# FLC_Circuit.net
KiCad netlist of a schematic drawn in EAGLE
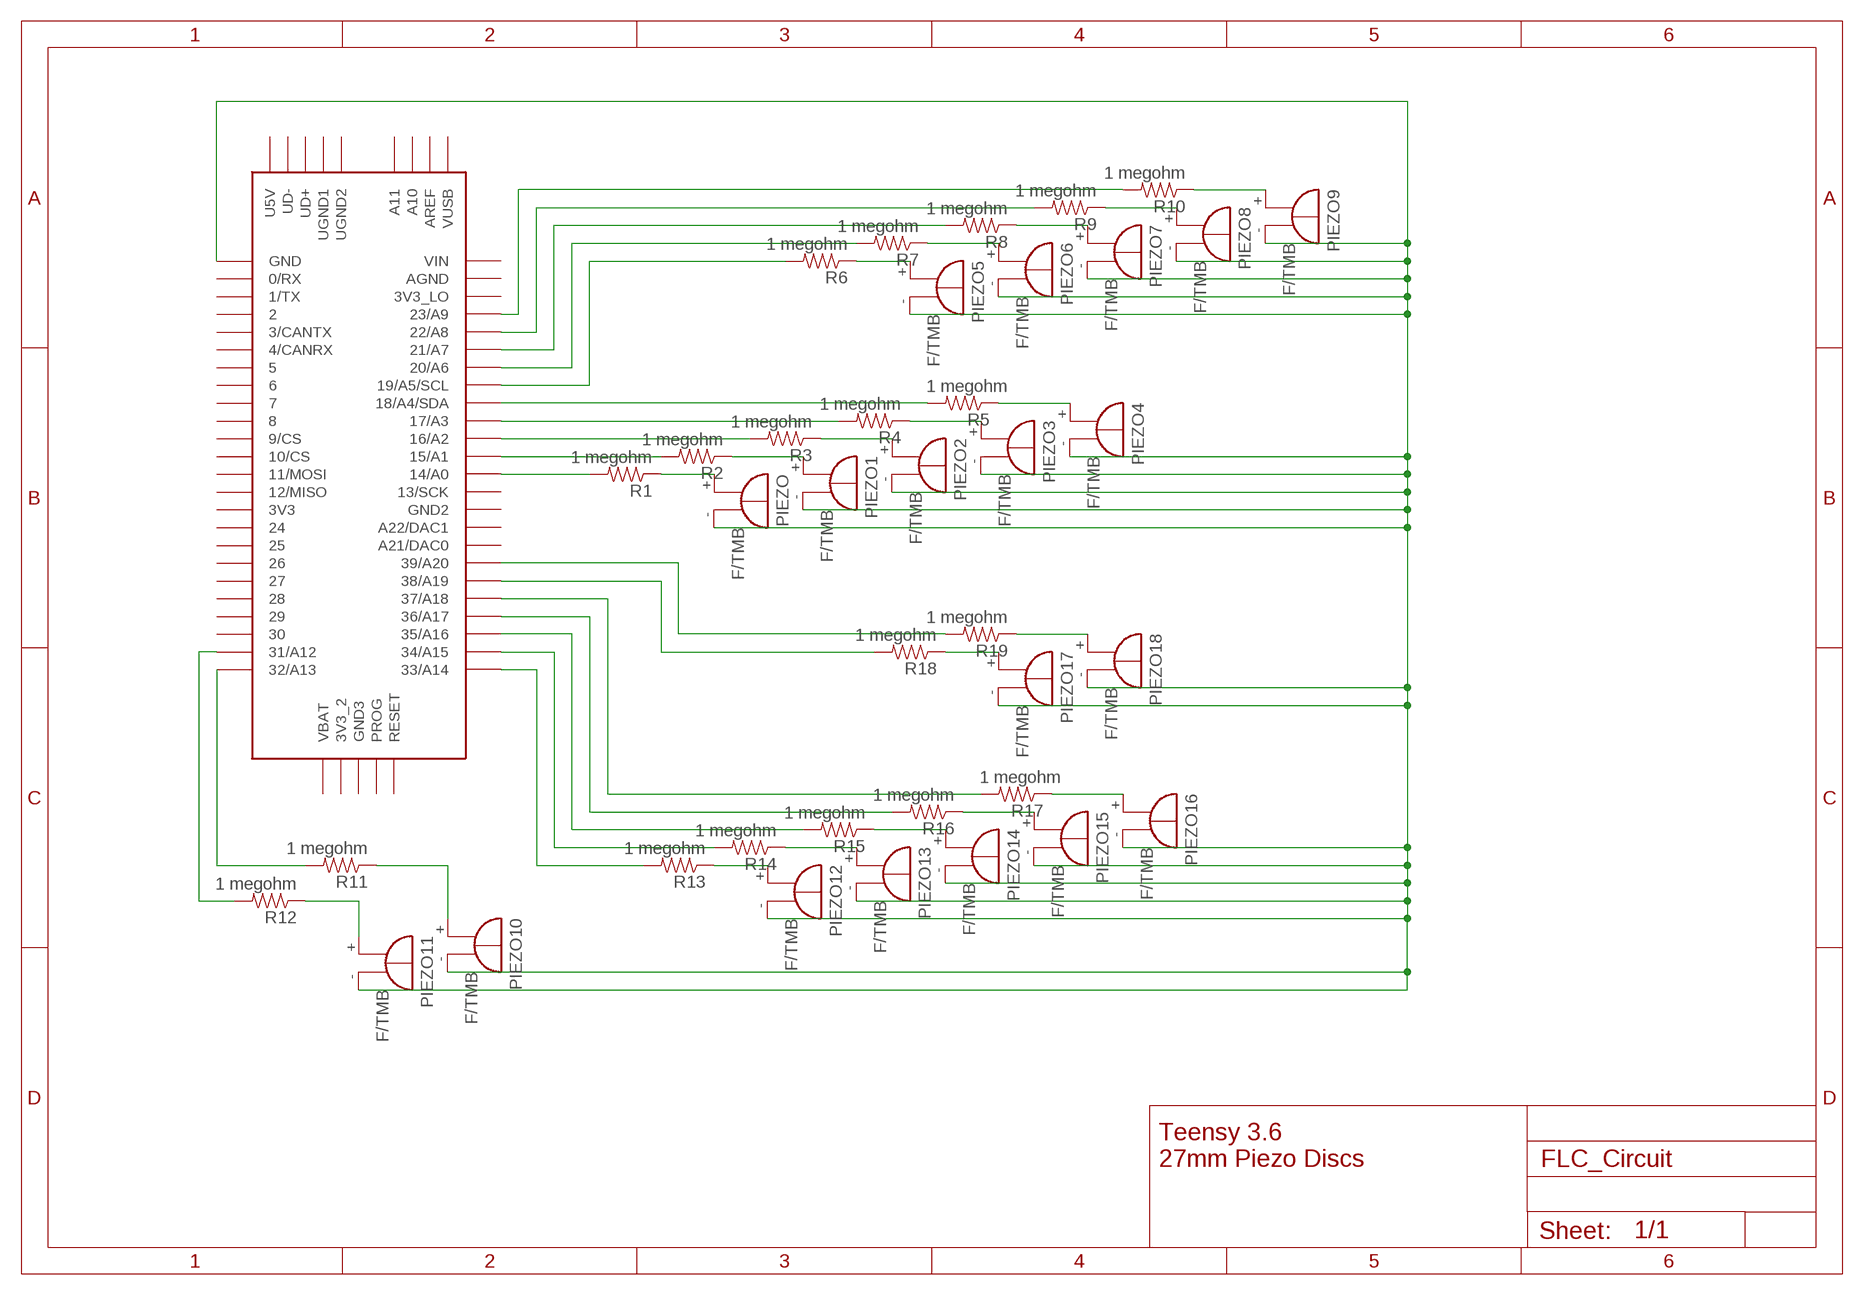
[diagram p0: schematic, sheet 1]

(export (version "E")
  (design (tool "Eeschema 10.0.6"))
  (components
    (comp (ref "PIEZO")
      (value "F/TMB")
      (footprint "eagle-import:F_TMB")
      (libsource (lib "eagle-import") (part "F/TMB"))
    )
    (comp (ref "PIEZO1")
      (value "F/TMB")
      (footprint "eagle-import:F_TMB")
      (libsource (lib "eagle-import") (part "F/TMB"))
    )
    (comp (ref "PIEZO2")
      (value "F/TMB")
      (footprint "eagle-import:F_TMB")
      (libsource (lib "eagle-import") (part "F/TMB"))
    )
    (comp (ref "PIEZO3")
      (value "F/TMB")
      (footprint "eagle-import:F_TMB")
      (libsource (lib "eagle-import") (part "F/TMB"))
    )
    (comp (ref "PIEZO4")
      (value "F/TMB")
      (footprint "eagle-import:F_TMB")
      (libsource (lib "eagle-import") (part "F/TMB"))
    )
    (comp (ref "PIEZO5")
      (value "F/TMB")
      (footprint "eagle-import:F_TMB")
      (libsource (lib "eagle-import") (part "F/TMB"))
    )
    (comp (ref "PIEZO6")
      (value "F/TMB")
      (footprint "eagle-import:F_TMB")
      (libsource (lib "eagle-import") (part "F/TMB"))
    )
    (comp (ref "PIEZO7")
      (value "F/TMB")
      (footprint "eagle-import:F_TMB")
      (libsource (lib "eagle-import") (part "F/TMB"))
    )
    (comp (ref "PIEZO8")
      (value "F/TMB")
      (footprint "eagle-import:F_TMB")
      (libsource (lib "eagle-import") (part "F/TMB"))
    )
    (comp (ref "PIEZO9")
      (value "F/TMB")
      (footprint "eagle-import:F_TMB")
      (libsource (lib "eagle-import") (part "F/TMB"))
    )
    (comp (ref "PIEZO10")
      (value "F/TMB")
      (footprint "eagle-import:F_TMB")
      (libsource (lib "eagle-import") (part "F/TMB"))
    )
    (comp (ref "PIEZO11")
      (value "F/TMB")
      (footprint "eagle-import:F_TMB")
      (libsource (lib "eagle-import") (part "F/TMB"))
    )
    (comp (ref "PIEZO12")
      (value "F/TMB")
      (footprint "eagle-import:F_TMB")
      (libsource (lib "eagle-import") (part "F/TMB"))
    )
    (comp (ref "PIEZO13")
      (value "F/TMB")
      (footprint "eagle-import:F_TMB")
      (libsource (lib "eagle-import") (part "F/TMB"))
    )
    (comp (ref "PIEZO14")
      (value "F/TMB")
      (footprint "eagle-import:F_TMB")
      (libsource (lib "eagle-import") (part "F/TMB"))
    )
    (comp (ref "PIEZO15")
      (value "F/TMB")
      (footprint "eagle-import:F_TMB")
      (libsource (lib "eagle-import") (part "F/TMB"))
    )
    (comp (ref "PIEZO16")
      (value "F/TMB")
      (footprint "eagle-import:F_TMB")
      (libsource (lib "eagle-import") (part "F/TMB"))
    )
    (comp (ref "PIEZO17")
      (value "F/TMB")
      (footprint "eagle-import:F_TMB")
      (libsource (lib "eagle-import") (part "F/TMB"))
    )
    (comp (ref "PIEZO18")
      (value "F/TMB")
      (footprint "eagle-import:F_TMB")
      (libsource (lib "eagle-import") (part "F/TMB"))
    )
    (comp (ref "R1")
      (value "1 megohm")
      (footprint "eagle-import:0805")
      (libsource (lib "eagle-import") (part "COMPONENT_RESISTOR-0805"))
    )
    (comp (ref "R2")
      (value "1 megohm")
      (footprint "eagle-import:0805")
      (libsource (lib "eagle-import") (part "COMPONENT_RESISTOR-0805"))
    )
    (comp (ref "R3")
      (value "1 megohm")
      (footprint "eagle-import:0805")
      (libsource (lib "eagle-import") (part "COMPONENT_RESISTOR-0805"))
    )
    (comp (ref "R4")
      (value "1 megohm")
      (footprint "eagle-import:0805")
      (libsource (lib "eagle-import") (part "COMPONENT_RESISTOR-0805"))
    )
    (comp (ref "R5")
      (value "1 megohm")
      (footprint "eagle-import:0805")
      (libsource (lib "eagle-import") (part "COMPONENT_RESISTOR-0805"))
    )
    (comp (ref "R6")
      (value "1 megohm")
      (footprint "eagle-import:0805")
      (libsource (lib "eagle-import") (part "COMPONENT_RESISTOR-0805"))
    )
    (comp (ref "R7")
      (value "1 megohm")
      (footprint "eagle-import:0805")
      (libsource (lib "eagle-import") (part "COMPONENT_RESISTOR-0805"))
    )
    (comp (ref "R8")
      (value "1 megohm")
      (footprint "eagle-import:0805")
      (libsource (lib "eagle-import") (part "COMPONENT_RESISTOR-0805"))
    )
    (comp (ref "R9")
      (value "1 megohm")
      (footprint "eagle-import:0805")
      (libsource (lib "eagle-import") (part "COMPONENT_RESISTOR-0805"))
    )
    (comp (ref "R10")
      (value "1 megohm")
      (footprint "eagle-import:0805")
      (libsource (lib "eagle-import") (part "COMPONENT_RESISTOR-0805"))
    )
    (comp (ref "R11")
      (value "1 megohm")
      (footprint "eagle-import:0805")
      (libsource (lib "eagle-import") (part "COMPONENT_RESISTOR-0805"))
    )
    (comp (ref "R12")
      (value "1 megohm")
      (footprint "eagle-import:0805")
      (libsource (lib "eagle-import") (part "COMPONENT_RESISTOR-0805"))
    )
    (comp (ref "R13")
      (value "1 megohm")
      (footprint "eagle-import:0805")
      (libsource (lib "eagle-import") (part "COMPONENT_RESISTOR-0805"))
    )
    (comp (ref "R14")
      (value "1 megohm")
      (footprint "eagle-import:0805")
      (libsource (lib "eagle-import") (part "COMPONENT_RESISTOR-0805"))
    )
    (comp (ref "R15")
      (value "1 megohm")
      (footprint "eagle-import:0805")
      (libsource (lib "eagle-import") (part "COMPONENT_RESISTOR-0805"))
    )
    (comp (ref "R16")
      (value "1 megohm")
      (footprint "eagle-import:0805")
      (libsource (lib "eagle-import") (part "COMPONENT_RESISTOR-0805"))
    )
    (comp (ref "R17")
      (value "1 megohm")
      (footprint "eagle-import:0805")
      (libsource (lib "eagle-import") (part "COMPONENT_RESISTOR-0805"))
    )
    (comp (ref "R18")
      (value "1 megohm")
      (footprint "eagle-import:0805")
      (libsource (lib "eagle-import") (part "COMPONENT_RESISTOR-0805"))
    )
    (comp (ref "R19")
      (value "1 megohm")
      (footprint "eagle-import:0805")
      (libsource (lib "eagle-import") (part "COMPONENT_RESISTOR-0805"))
    )
    (comp (ref "U$1")
      (value "TEENSY_3.5/3.6")
      (footprint "eagle-import:TEENSY_3.5_3.6")
      (libsource (lib "eagle-import") (part "TEENSY_3.5/3.6"))
    )
  )
  (nets
    (net (code "1") (name "Net-(PIEZO-Pad+)") (class "Default")
      (node (ref "PIEZO") (pin "+") (pinfunction "+_+") (pintype "passive"))
      (node (ref "R1") (pin "1") (pinfunction "1_1") (pintype "passive"))
    )
    (net (code "2") (name "Net-(PIEZO-Pad-)") (class "Default")
      (node (ref "PIEZO") (pin "-") (pinfunction "-_-") (pintype "passive"))
      (node (ref "PIEZO1") (pin "-") (pinfunction "-_-") (pintype "passive"))
      (node (ref "PIEZO10") (pin "-") (pinfunction "-_-") (pintype "passive"))
      (node (ref "PIEZO11") (pin "-") (pinfunction "-_-") (pintype "passive"))
      (node (ref "PIEZO12") (pin "-") (pinfunction "-_-") (pintype "passive"))
      (node (ref "PIEZO13") (pin "-") (pinfunction "-_-") (pintype "passive"))
      (node (ref "PIEZO14") (pin "-") (pinfunction "-_-") (pintype "passive"))
      (node (ref "PIEZO15") (pin "-") (pinfunction "-_-") (pintype "passive"))
      (node (ref "PIEZO16") (pin "-") (pinfunction "-_-") (pintype "passive"))
      (node (ref "PIEZO17") (pin "-") (pinfunction "-_-") (pintype "passive"))
      (node (ref "PIEZO18") (pin "-") (pinfunction "-_-") (pintype "passive"))
      (node (ref "PIEZO2") (pin "-") (pinfunction "-_-") (pintype "passive"))
      (node (ref "PIEZO3") (pin "-") (pinfunction "-_-") (pintype "passive"))
      (node (ref "PIEZO4") (pin "-") (pinfunction "-_-") (pintype "passive"))
      (node (ref "PIEZO5") (pin "-") (pinfunction "-_-") (pintype "passive"))
      (node (ref "PIEZO6") (pin "-") (pinfunction "-_-") (pintype "passive"))
      (node (ref "PIEZO7") (pin "-") (pinfunction "-_-") (pintype "passive"))
      (node (ref "PIEZO8") (pin "-") (pinfunction "-_-") (pintype "passive"))
      (node (ref "PIEZO9") (pin "-") (pinfunction "-_-") (pintype "passive"))
      (node (ref "U$1") (pin "GND") (pinfunction "GND_GND") (pintype "bidirectional"))
    )
    (net (code "3") (name "Net-(PIEZO1-Pad+)") (class "Default")
      (node (ref "PIEZO1") (pin "+") (pinfunction "+_+") (pintype "passive"))
      (node (ref "R2") (pin "1") (pinfunction "1_1") (pintype "passive"))
    )
    (net (code "4") (name "Net-(PIEZO2-Pad+)") (class "Default")
      (node (ref "PIEZO2") (pin "+") (pinfunction "+_+") (pintype "passive"))
      (node (ref "R3") (pin "1") (pinfunction "1_1") (pintype "passive"))
    )
    (net (code "5") (name "Net-(PIEZO3-Pad+)") (class "Default")
      (node (ref "PIEZO3") (pin "+") (pinfunction "+_+") (pintype "passive"))
      (node (ref "R4") (pin "1") (pinfunction "1_1") (pintype "passive"))
    )
    (net (code "6") (name "Net-(PIEZO4-Pad+)") (class "Default")
      (node (ref "PIEZO4") (pin "+") (pinfunction "+_+") (pintype "passive"))
      (node (ref "R5") (pin "1") (pinfunction "1_1") (pintype "passive"))
    )
    (net (code "7") (name "Net-(PIEZO5-Pad+)") (class "Default")
      (node (ref "PIEZO5") (pin "+") (pinfunction "+_+") (pintype "passive"))
      (node (ref "R6") (pin "1") (pinfunction "1_1") (pintype "passive"))
    )
    (net (code "8") (name "Net-(PIEZO6-Pad+)") (class "Default")
      (node (ref "PIEZO6") (pin "+") (pinfunction "+_+") (pintype "passive"))
      (node (ref "R7") (pin "1") (pinfunction "1_1") (pintype "passive"))
    )
    (net (code "9") (name "Net-(PIEZO7-Pad+)") (class "Default")
      (node (ref "PIEZO7") (pin "+") (pinfunction "+_+") (pintype "passive"))
      (node (ref "R8") (pin "1") (pinfunction "1_1") (pintype "passive"))
    )
    (net (code "10") (name "Net-(PIEZO8-Pad+)") (class "Default")
      (node (ref "PIEZO8") (pin "+") (pinfunction "+_+") (pintype "passive"))
      (node (ref "R9") (pin "1") (pinfunction "1_1") (pintype "passive"))
    )
    (net (code "11") (name "Net-(PIEZO9-Pad+)") (class "Default")
      (node (ref "PIEZO9") (pin "+") (pinfunction "+_+") (pintype "passive"))
      (node (ref "R10") (pin "1") (pinfunction "1_1") (pintype "passive"))
    )
    (net (code "12") (name "Net-(PIEZO10-Pad+)") (class "Default")
      (node (ref "PIEZO10") (pin "+") (pinfunction "+_+") (pintype "passive"))
      (node (ref "R11") (pin "1") (pinfunction "1_1") (pintype "passive"))
    )
    (net (code "13") (name "Net-(PIEZO11-Pad+)") (class "Default")
      (node (ref "PIEZO11") (pin "+") (pinfunction "+_+") (pintype "passive"))
      (node (ref "R12") (pin "1") (pinfunction "1_1") (pintype "passive"))
    )
    (net (code "14") (name "Net-(PIEZO12-Pad+)") (class "Default")
      (node (ref "PIEZO12") (pin "+") (pinfunction "+_+") (pintype "passive"))
      (node (ref "R13") (pin "1") (pinfunction "1_1") (pintype "passive"))
    )
    (net (code "15") (name "Net-(PIEZO13-Pad+)") (class "Default")
      (node (ref "PIEZO13") (pin "+") (pinfunction "+_+") (pintype "passive"))
      (node (ref "R14") (pin "1") (pinfunction "1_1") (pintype "passive"))
    )
    (net (code "16") (name "Net-(PIEZO14-Pad+)") (class "Default")
      (node (ref "PIEZO14") (pin "+") (pinfunction "+_+") (pintype "passive"))
      (node (ref "R15") (pin "1") (pinfunction "1_1") (pintype "passive"))
    )
    (net (code "17") (name "Net-(PIEZO15-Pad+)") (class "Default")
      (node (ref "PIEZO15") (pin "+") (pinfunction "+_+") (pintype "passive"))
      (node (ref "R16") (pin "1") (pinfunction "1_1") (pintype "passive"))
    )
    (net (code "18") (name "Net-(PIEZO16-Pad+)") (class "Default")
      (node (ref "PIEZO16") (pin "+") (pinfunction "+_+") (pintype "passive"))
      (node (ref "R17") (pin "1") (pinfunction "1_1") (pintype "passive"))
    )
    (net (code "19") (name "Net-(PIEZO17-Pad+)") (class "Default")
      (node (ref "PIEZO17") (pin "+") (pinfunction "+_+") (pintype "passive"))
      (node (ref "R18") (pin "1") (pinfunction "1_1") (pintype "passive"))
    )
    (net (code "20") (name "Net-(PIEZO18-Pad+)") (class "Default")
      (node (ref "PIEZO18") (pin "+") (pinfunction "+_+") (pintype "passive"))
      (node (ref "R19") (pin "1") (pinfunction "1_1") (pintype "passive"))
    )
    (net (code "21") (name "Net-(R1-Pad2)") (class "Default")
      (node (ref "R1") (pin "2") (pinfunction "2_2") (pintype "passive"))
      (node (ref "U$1") (pin "14/A0") (pinfunction "14/A0_14/A0") (pintype "bidirectional"))
    )
    (net (code "22") (name "Net-(R2-Pad2)") (class "Default")
      (node (ref "R2") (pin "2") (pinfunction "2_2") (pintype "passive"))
      (node (ref "U$1") (pin "15/A1") (pinfunction "15/A1_15/A1") (pintype "bidirectional"))
    )
    (net (code "23") (name "Net-(R3-Pad2)") (class "Default")
      (node (ref "R3") (pin "2") (pinfunction "2_2") (pintype "passive"))
      (node (ref "U$1") (pin "16/A2") (pinfunction "16/A2_16/A2") (pintype "bidirectional"))
    )
    (net (code "24") (name "Net-(R4-Pad2)") (class "Default")
      (node (ref "R4") (pin "2") (pinfunction "2_2") (pintype "passive"))
      (node (ref "U$1") (pin "17/A3") (pinfunction "17/A3_17/A3") (pintype "bidirectional"))
    )
    (net (code "25") (name "Net-(R5-Pad2)") (class "Default")
      (node (ref "R5") (pin "2") (pinfunction "2_2") (pintype "passive"))
      (node (ref "U$1") (pin "18/A4/SDA") (pinfunction "18/A4/SDA_18/A4/SDA") (pintype "bidirectional"))
    )
    (net (code "26") (name "Net-(R6-Pad2)") (class "Default")
      (node (ref "R6") (pin "2") (pinfunction "2_2") (pintype "passive"))
      (node (ref "U$1") (pin "19/A5/SCL") (pinfunction "19/A5/SCL_19/A5/SCL") (pintype "bidirectional"))
    )
    (net (code "27") (name "Net-(R7-Pad2)") (class "Default")
      (node (ref "R7") (pin "2") (pinfunction "2_2") (pintype "passive"))
      (node (ref "U$1") (pin "20/A6") (pinfunction "20/A6_20/A6") (pintype "bidirectional"))
    )
    (net (code "28") (name "Net-(R8-Pad2)") (class "Default")
      (node (ref "R8") (pin "2") (pinfunction "2_2") (pintype "passive"))
      (node (ref "U$1") (pin "21/A7") (pinfunction "21/A7_21/A7") (pintype "bidirectional"))
    )
    (net (code "29") (name "Net-(R9-Pad2)") (class "Default")
      (node (ref "R9") (pin "2") (pinfunction "2_2") (pintype "passive"))
      (node (ref "U$1") (pin "22/A8") (pinfunction "22/A8_22/A8") (pintype "bidirectional"))
    )
    (net (code "30") (name "Net-(R10-Pad2)") (class "Default")
      (node (ref "R10") (pin "2") (pinfunction "2_2") (pintype "passive"))
      (node (ref "U$1") (pin "23/A9") (pinfunction "23/A9_23/A9") (pintype "bidirectional"))
    )
    (net (code "31") (name "Net-(R11-Pad2)") (class "Default")
      (node (ref "R11") (pin "2") (pinfunction "2_2") (pintype "passive"))
      (node (ref "U$1") (pin "32/A13") (pinfunction "32/A13_32/A13") (pintype "bidirectional"))
    )
    (net (code "32") (name "Net-(R12-Pad2)") (class "Default")
      (node (ref "R12") (pin "2") (pinfunction "2_2") (pintype "passive"))
      (node (ref "U$1") (pin "31/A12") (pinfunction "31/A12_31/A12") (pintype "bidirectional"))
    )
    (net (code "33") (name "Net-(R13-Pad2)") (class "Default")
      (node (ref "R13") (pin "2") (pinfunction "2_2") (pintype "passive"))
      (node (ref "U$1") (pin "33/A14") (pinfunction "33/A14_33/A14") (pintype "bidirectional"))
    )
    (net (code "34") (name "Net-(R14-Pad2)") (class "Default")
      (node (ref "R14") (pin "2") (pinfunction "2_2") (pintype "passive"))
      (node (ref "U$1") (pin "34/A15") (pinfunction "34/A15_34/A15") (pintype "bidirectional"))
    )
    (net (code "35") (name "Net-(R15-Pad2)") (class "Default")
      (node (ref "R15") (pin "2") (pinfunction "2_2") (pintype "passive"))
      (node (ref "U$1") (pin "35/A16") (pinfunction "35/A16_35/A16") (pintype "bidirectional"))
    )
    (net (code "36") (name "Net-(R16-Pad2)") (class "Default")
      (node (ref "R16") (pin "2") (pinfunction "2_2") (pintype "passive"))
      (node (ref "U$1") (pin "36/A17") (pinfunction "36/A17_36/A17") (pintype "bidirectional"))
    )
    (net (code "37") (name "Net-(R17-Pad2)") (class "Default")
      (node (ref "R17") (pin "2") (pinfunction "2_2") (pintype "passive"))
      (node (ref "U$1") (pin "37/A18") (pinfunction "37/A18_37/A18") (pintype "bidirectional"))
    )
    (net (code "38") (name "Net-(R18-Pad2)") (class "Default")
      (node (ref "R18") (pin "2") (pinfunction "2_2") (pintype "passive"))
      (node (ref "U$1") (pin "38/A19") (pinfunction "38/A19_38/A19") (pintype "bidirectional"))
    )
    (net (code "39") (name "Net-(R19-Pad2)") (class "Default")
      (node (ref "R19") (pin "2") (pinfunction "2_2") (pintype "passive"))
      (node (ref "U$1") (pin "39/A20") (pinfunction "39/A20_39/A20") (pintype "bidirectional"))
    )
    (net (code "40") (name "unconnected-(U$1-A21{slash}DAC0-Pad21{slash}DAC0)") (class "Default")
      (node (ref "U$1") (pin "21/DAC0") (pinfunction "A21/DAC0_21/DAC0") (pintype "bidirectional"))
    )
    (net (code "41") (name "unconnected-(U$1-Pad0{slash}RX)") (class "Default")
      (node (ref "U$1") (pin "0/RX") (pinfunction "0/RX_0/RX") (pintype "bidirectional"))
    )
    (net (code "42") (name "unconnected-(U$1-Pad1{slash}TX)") (class "Default")
      (node (ref "U$1") (pin "1/TX") (pinfunction "1/TX_1/TX") (pintype "bidirectional"))
    )
    (net (code "43") (name "unconnected-(U$1-Pad2)") (class "Default")
      (node (ref "U$1") (pin "2") (pinfunction "2_2") (pintype "bidirectional"))
    )
    (net (code "44") (name "unconnected-(U$1-Pad3V3)") (class "Default")
      (node (ref "U$1") (pin "3V3") (pinfunction "3V3_3V3") (pintype "bidirectional"))
    )
    (net (code "45") (name "unconnected-(U$1-Pad3V3_2)") (class "Default")
      (node (ref "U$1") (pin "3V3_2") (pinfunction "3V3_2_3V3_2") (pintype "bidirectional"))
    )
    (net (code "46") (name "unconnected-(U$1-Pad3V3_LO)") (class "Default")
      (node (ref "U$1") (pin "3V3_LO") (pinfunction "3V3_LO_3V3_LO") (pintype "bidirectional"))
    )
    (net (code "47") (name "unconnected-(U$1-Pad3{slash}CANTX)") (class "Default")
      (node (ref "U$1") (pin "3/CANTX") (pinfunction "3/CANTX_3/CANTX") (pintype "bidirectional"))
    )
    (net (code "48") (name "unconnected-(U$1-Pad4{slash}CANRX)") (class "Default")
      (node (ref "U$1") (pin "4/CANRX") (pinfunction "4/CANRX_4/CANRX") (pintype "bidirectional"))
    )
    (net (code "49") (name "unconnected-(U$1-Pad5)") (class "Default")
      (node (ref "U$1") (pin "5") (pinfunction "5_5") (pintype "bidirectional"))
    )
    (net (code "50") (name "unconnected-(U$1-Pad6)") (class "Default")
      (node (ref "U$1") (pin "6") (pinfunction "6_6") (pintype "bidirectional"))
    )
    (net (code "51") (name "unconnected-(U$1-Pad7)") (class "Default")
      (node (ref "U$1") (pin "7") (pinfunction "7_7") (pintype "bidirectional"))
    )
    (net (code "52") (name "unconnected-(U$1-Pad8)") (class "Default")
      (node (ref "U$1") (pin "8") (pinfunction "8_8") (pintype "bidirectional"))
    )
    (net (code "53") (name "unconnected-(U$1-Pad9{slash}CS)") (class "Default")
      (node (ref "U$1") (pin "9/CS") (pinfunction "9/CS_9/CS") (pintype "bidirectional"))
    )
    (net (code "54") (name "unconnected-(U$1-Pad10{slash}CS)") (class "Default")
      (node (ref "U$1") (pin "10/CS") (pinfunction "10/CS_10/CS") (pintype "bidirectional"))
    )
    (net (code "55") (name "unconnected-(U$1-Pad11{slash}MOSI)") (class "Default")
      (node (ref "U$1") (pin "11/MOSI") (pinfunction "11/MOSI_11/MOSI") (pintype "bidirectional"))
    )
    (net (code "56") (name "unconnected-(U$1-Pad12{slash}MISO)") (class "Default")
      (node (ref "U$1") (pin "12/MISO") (pinfunction "12/MISO_12/MISO") (pintype "bidirectional"))
    )
    (net (code "57") (name "unconnected-(U$1-Pad13{slash}SCK)") (class "Default")
      (node (ref "U$1") (pin "13/SCK") (pinfunction "13/SCK_13/SCK") (pintype "bidirectional"))
    )
    (net (code "58") (name "unconnected-(U$1-Pad24)") (class "Default")
      (node (ref "U$1") (pin "24") (pinfunction "24_24") (pintype "bidirectional"))
    )
    (net (code "59") (name "unconnected-(U$1-Pad25)") (class "Default")
      (node (ref "U$1") (pin "25") (pinfunction "25_25") (pintype "bidirectional"))
    )
    (net (code "60") (name "unconnected-(U$1-Pad26)") (class "Default")
      (node (ref "U$1") (pin "26") (pinfunction "26_26") (pintype "bidirectional"))
    )
    (net (code "61") (name "unconnected-(U$1-Pad27)") (class "Default")
      (node (ref "U$1") (pin "27") (pinfunction "27_27") (pintype "bidirectional"))
    )
    (net (code "62") (name "unconnected-(U$1-Pad28)") (class "Default")
      (node (ref "U$1") (pin "28") (pinfunction "28_28") (pintype "bidirectional"))
    )
    (net (code "63") (name "unconnected-(U$1-Pad29)") (class "Default")
      (node (ref "U$1") (pin "29") (pinfunction "29_29") (pintype "bidirectional"))
    )
    (net (code "64") (name "unconnected-(U$1-Pad30)") (class "Default")
      (node (ref "U$1") (pin "30") (pinfunction "30_30") (pintype "bidirectional"))
    )
    (net (code "65") (name "unconnected-(U$1-PadA10)") (class "Default")
      (node (ref "U$1") (pin "A10") (pinfunction "A10_A10") (pintype "bidirectional"))
    )
    (net (code "66") (name "unconnected-(U$1-PadA11)") (class "Default")
      (node (ref "U$1") (pin "A11") (pinfunction "A11_A11") (pintype "bidirectional"))
    )
    (net (code "67") (name "unconnected-(U$1-PadA22{slash}DAC1)") (class "Default")
      (node (ref "U$1") (pin "A22/DAC1") (pinfunction "A22/DAC1_A22/DAC1") (pintype "bidirectional"))
    )
    (net (code "68") (name "unconnected-(U$1-PadAGND)") (class "Default")
      (node (ref "U$1") (pin "AGND") (pinfunction "AGND_AGND") (pintype "bidirectional"))
    )
    (net (code "69") (name "unconnected-(U$1-PadAREF)") (class "Default")
      (node (ref "U$1") (pin "AREF") (pinfunction "AREF_AREF") (pintype "bidirectional"))
    )
    (net (code "70") (name "unconnected-(U$1-PadGND2)") (class "Default")
      (node (ref "U$1") (pin "GND2") (pinfunction "GND2_GND2") (pintype "bidirectional"))
    )
    (net (code "71") (name "unconnected-(U$1-PadGND3)") (class "Default")
      (node (ref "U$1") (pin "GND3") (pinfunction "GND3_GND3") (pintype "bidirectional"))
    )
    (net (code "72") (name "unconnected-(U$1-PadPROG)") (class "Default")
      (node (ref "U$1") (pin "PROG") (pinfunction "PROG_PROG") (pintype "bidirectional"))
    )
    (net (code "73") (name "unconnected-(U$1-PadRESET)") (class "Default")
      (node (ref "U$1") (pin "RESET") (pinfunction "RESET_RESET") (pintype "bidirectional"))
    )
    (net (code "74") (name "unconnected-(U$1-PadU5V)") (class "Default")
      (node (ref "U$1") (pin "U5V") (pinfunction "U5V_U5V") (pintype "bidirectional"))
    )
    (net (code "75") (name "unconnected-(U$1-PadUD+)") (class "Default")
      (node (ref "U$1") (pin "UD+") (pinfunction "UD+_UD+") (pintype "bidirectional"))
    )
    (net (code "76") (name "unconnected-(U$1-PadUD-)") (class "Default")
      (node (ref "U$1") (pin "UD-") (pinfunction "UD-_UD-") (pintype "bidirectional"))
    )
    (net (code "77") (name "unconnected-(U$1-PadUGND1)") (class "Default")
      (node (ref "U$1") (pin "UGND1") (pinfunction "UGND1_UGND1") (pintype "bidirectional"))
    )
    (net (code "78") (name "unconnected-(U$1-PadUGND2)") (class "Default")
      (node (ref "U$1") (pin "UGND2") (pinfunction "UGND2_UGND2") (pintype "bidirectional"))
    )
    (net (code "79") (name "unconnected-(U$1-PadVBAT)") (class "Default")
      (node (ref "U$1") (pin "VBAT") (pinfunction "VBAT_VBAT") (pintype "bidirectional"))
    )
    (net (code "80") (name "unconnected-(U$1-PadVIN)") (class "Default")
      (node (ref "U$1") (pin "VIN") (pinfunction "VIN_VIN") (pintype "bidirectional"))
    )
    (net (code "81") (name "unconnected-(U$1-PadVUSB)") (class "Default")
      (node (ref "U$1") (pin "VUSB") (pinfunction "VUSB_VUSB") (pintype "bidirectional"))
    )
  )
)
